# BMS.net
KiCad netlist of a schematic drawn in EAGLE
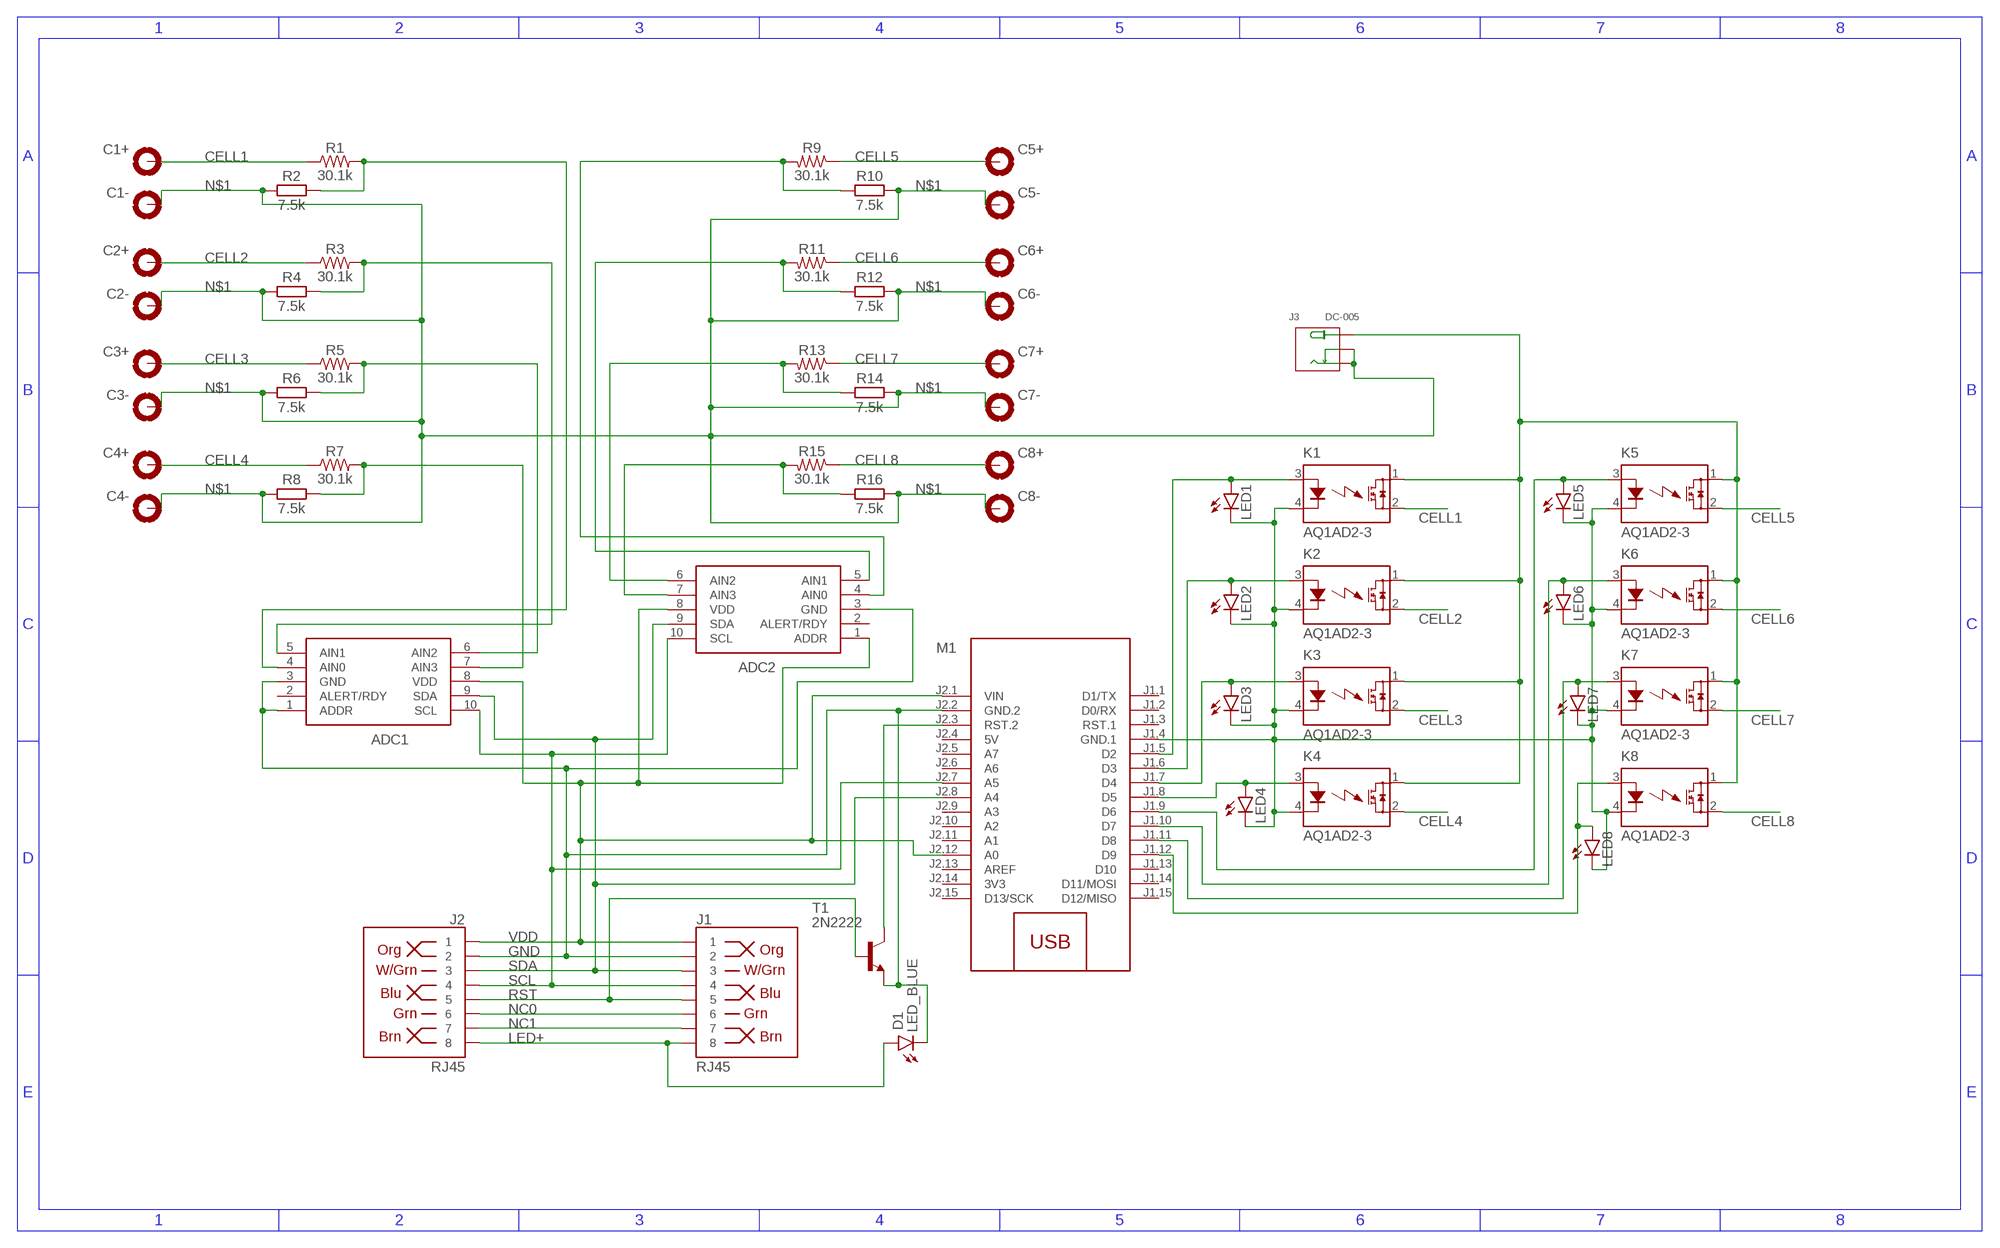
[diagram p0: schematic, sheet 1]

(export (version "E")
  (design (tool "Eeschema 10.0.6"))
  (components
    (comp (ref "ADC1")
      (value "ADS1115IDGST")
      (footprint "eagle-import:SOP50P490X110-10N")
      (fields (field (name "MOUSER_PART_NUMBER") "595-ADS1115IDGST"))
      (libsource (lib "eagle-import") (part "ADS1115IDGST"))
    )
    (comp (ref "ADC2")
      (value "ADS1115IDGST")
      (footprint "eagle-import:SOP50P490X110-10N")
      (fields (field (name "MOUSER_PART_NUMBER") "595-ADS1115IDGST"))
      (libsource (lib "eagle-import") (part "ADS1115IDGST"))
    )
    (comp (ref "C1+")
      (value "HOLES_MOUNT-PAD-ROUND-0.096-NS")
      (footprint "eagle-import:HOLES_096-PAD-NS")
      (libsource (lib "eagle-import") (part "HOLES_MOUNT-PAD-ROUND-0.096-NS"))
    )
    (comp (ref "C1-")
      (value "HOLES_MOUNT-PAD-ROUND-0.096-NS")
      (footprint "eagle-import:HOLES_096-PAD-NS")
      (libsource (lib "eagle-import") (part "HOLES_MOUNT-PAD-ROUND-0.096-NS"))
    )
    (comp (ref "C2+")
      (value "HOLES_MOUNT-PAD-ROUND-0.096-NS")
      (footprint "eagle-import:HOLES_096-PAD-NS")
      (libsource (lib "eagle-import") (part "HOLES_MOUNT-PAD-ROUND-0.096-NS"))
    )
    (comp (ref "C2-")
      (value "HOLES_MOUNT-PAD-ROUND-0.096-NS")
      (footprint "eagle-import:HOLES_096-PAD-NS")
      (libsource (lib "eagle-import") (part "HOLES_MOUNT-PAD-ROUND-0.096-NS"))
    )
    (comp (ref "C3+")
      (value "HOLES_MOUNT-PAD-ROUND-0.096-NS")
      (footprint "eagle-import:HOLES_096-PAD-NS")
      (libsource (lib "eagle-import") (part "HOLES_MOUNT-PAD-ROUND-0.096-NS"))
    )
    (comp (ref "C3-")
      (value "HOLES_MOUNT-PAD-ROUND-0.096-NS")
      (footprint "eagle-import:HOLES_096-PAD-NS")
      (libsource (lib "eagle-import") (part "HOLES_MOUNT-PAD-ROUND-0.096-NS"))
    )
    (comp (ref "C4+")
      (value "HOLES_MOUNT-PAD-ROUND-0.096-NS")
      (footprint "eagle-import:HOLES_096-PAD-NS")
      (libsource (lib "eagle-import") (part "HOLES_MOUNT-PAD-ROUND-0.096-NS"))
    )
    (comp (ref "C4-")
      (value "HOLES_MOUNT-PAD-ROUND-0.096-NS")
      (footprint "eagle-import:HOLES_096-PAD-NS")
      (libsource (lib "eagle-import") (part "HOLES_MOUNT-PAD-ROUND-0.096-NS"))
    )
    (comp (ref "C5+")
      (value "HOLES_MOUNT-PAD-ROUND-0.096-NS")
      (footprint "eagle-import:HOLES_096-PAD-NS")
      (libsource (lib "eagle-import") (part "HOLES_MOUNT-PAD-ROUND-0.096-NS"))
    )
    (comp (ref "C5-")
      (value "HOLES_MOUNT-PAD-ROUND-0.096-NS")
      (footprint "eagle-import:HOLES_096-PAD-NS")
      (libsource (lib "eagle-import") (part "HOLES_MOUNT-PAD-ROUND-0.096-NS"))
    )
    (comp (ref "C6+")
      (value "HOLES_MOUNT-PAD-ROUND-0.096-NS")
      (footprint "eagle-import:HOLES_096-PAD-NS")
      (libsource (lib "eagle-import") (part "HOLES_MOUNT-PAD-ROUND-0.096-NS"))
    )
    (comp (ref "C6-")
      (value "HOLES_MOUNT-PAD-ROUND-0.096-NS")
      (footprint "eagle-import:HOLES_096-PAD-NS")
      (libsource (lib "eagle-import") (part "HOLES_MOUNT-PAD-ROUND-0.096-NS"))
    )
    (comp (ref "C7+")
      (value "HOLES_MOUNT-PAD-ROUND-0.096-NS")
      (footprint "eagle-import:HOLES_096-PAD-NS")
      (libsource (lib "eagle-import") (part "HOLES_MOUNT-PAD-ROUND-0.096-NS"))
    )
    (comp (ref "C7-")
      (value "HOLES_MOUNT-PAD-ROUND-0.096-NS")
      (footprint "eagle-import:HOLES_096-PAD-NS")
      (libsource (lib "eagle-import") (part "HOLES_MOUNT-PAD-ROUND-0.096-NS"))
    )
    (comp (ref "C8+")
      (value "HOLES_MOUNT-PAD-ROUND-0.096-NS")
      (footprint "eagle-import:HOLES_096-PAD-NS")
      (libsource (lib "eagle-import") (part "HOLES_MOUNT-PAD-ROUND-0.096-NS"))
    )
    (comp (ref "C8-")
      (value "HOLES_MOUNT-PAD-ROUND-0.096-NS")
      (footprint "eagle-import:HOLES_096-PAD-NS")
      (libsource (lib "eagle-import") (part "HOLES_MOUNT-PAD-ROUND-0.096-NS"))
    )
    (comp (ref "D1")
      (value "LED_BLUE")
      (footprint "eagle-import:LEDRD254W60D565H860B_B")
      (libsource (lib "eagle-import") (part "LED_RADIALBLUE_"))
    )
    (comp (ref "J1")
      (value "RJ45")
      (footprint "eagle-import:RJ45-8")
      (libsource (lib "eagle-import") (part "RJ45-8"))
    )
    (comp (ref "J2")
      (value "RJ45")
      (footprint "eagle-import:RJ45-8")
      (libsource (lib "eagle-import") (part "RJ45-8"))
    )
    (comp (ref "J3")
      (value "DC-005")
      (footprint "eagle-import:DCJ3P-14.2X11.0X9.0MM")
      (libsource (lib "eagle-import") (part "CONN-POWER-JACK-2.1MM(DC-005)"))
    )
    (comp (ref "K1")
      (value "AQ1AD2-3")
      (footprint "eagle-import:AQ1")
      (fields (field (name "MF") "AROMAT/ MATSUSHITA") (field (name "MPN") "AQ1AD2-3/28VDC"))
      (libsource (lib "eagle-import") (part "AQ1AD2-3"))
    )
    (comp (ref "K2")
      (value "AQ1AD2-3")
      (footprint "eagle-import:AQ1")
      (fields (field (name "MF") "AROMAT/ MATSUSHITA") (field (name "MPN") "AQ1AD2-3/28VDC"))
      (libsource (lib "eagle-import") (part "AQ1AD2-3"))
    )
    (comp (ref "K3")
      (value "AQ1AD2-3")
      (footprint "eagle-import:AQ1")
      (fields (field (name "MF") "AROMAT/ MATSUSHITA") (field (name "MPN") "AQ1AD2-3/28VDC"))
      (libsource (lib "eagle-import") (part "AQ1AD2-3"))
    )
    (comp (ref "K4")
      (value "AQ1AD2-3")
      (footprint "eagle-import:AQ1")
      (fields (field (name "MF") "AROMAT/ MATSUSHITA") (field (name "MPN") "AQ1AD2-3/28VDC"))
      (libsource (lib "eagle-import") (part "AQ1AD2-3"))
    )
    (comp (ref "K5")
      (value "AQ1AD2-3")
      (footprint "eagle-import:AQ1")
      (fields (field (name "MF") "AROMAT/ MATSUSHITA") (field (name "MPN") "AQ1AD2-3/28VDC"))
      (libsource (lib "eagle-import") (part "AQ1AD2-3"))
    )
    (comp (ref "K6")
      (value "AQ1AD2-3")
      (footprint "eagle-import:AQ1")
      (fields (field (name "MF") "AROMAT/ MATSUSHITA") (field (name "MPN") "AQ1AD2-3/28VDC"))
      (libsource (lib "eagle-import") (part "AQ1AD2-3"))
    )
    (comp (ref "K7")
      (value "AQ1AD2-3")
      (footprint "eagle-import:AQ1")
      (fields (field (name "MF") "AROMAT/ MATSUSHITA") (field (name "MPN") "AQ1AD2-3/28VDC"))
      (libsource (lib "eagle-import") (part "AQ1AD2-3"))
    )
    (comp (ref "K8")
      (value "AQ1AD2-3")
      (footprint "eagle-import:AQ1")
      (fields (field (name "MF") "AROMAT/ MATSUSHITA") (field (name "MPN") "AQ1AD2-3/28VDC"))
      (libsource (lib "eagle-import") (part "AQ1AD2-3"))
    )
    (comp (ref "LED1")
      (value "LEDCHIP-LED0805")
      (footprint "eagle-import:CHIP-LED0805")
      (libsource (lib "eagle-import") (part "LEDCHIP-LED0805"))
    )
    (comp (ref "LED2")
      (value "LEDCHIP-LED0805")
      (footprint "eagle-import:CHIP-LED0805")
      (libsource (lib "eagle-import") (part "LEDCHIP-LED0805"))
    )
    (comp (ref "LED3")
      (value "LEDCHIP-LED0805")
      (footprint "eagle-import:CHIP-LED0805")
      (libsource (lib "eagle-import") (part "LEDCHIP-LED0805"))
    )
    (comp (ref "LED4")
      (value "LEDCHIP-LED0805")
      (footprint "eagle-import:CHIP-LED0805")
      (libsource (lib "eagle-import") (part "LEDCHIP-LED0805"))
    )
    (comp (ref "LED5")
      (value "LEDCHIP-LED0805")
      (footprint "eagle-import:CHIP-LED0805")
      (libsource (lib "eagle-import") (part "LEDCHIP-LED0805"))
    )
    (comp (ref "LED6")
      (value "LEDCHIP-LED0805")
      (footprint "eagle-import:CHIP-LED0805")
      (libsource (lib "eagle-import") (part "LEDCHIP-LED0805"))
    )
    (comp (ref "LED7")
      (value "LEDCHIP-LED0805")
      (footprint "eagle-import:CHIP-LED0805")
      (libsource (lib "eagle-import") (part "LEDCHIP-LED0805"))
    )
    (comp (ref "LED8")
      (value "LEDCHIP-LED0805")
      (footprint "eagle-import:CHIP-LED0805")
      (libsource (lib "eagle-import") (part "LEDCHIP-LED0805"))
    )
    (comp (ref "M1")
      (value "ARDUINO-NANO-3.0")
      (footprint "eagle-import:ARDUINO-NANO-3.0")
      (libsource (lib "eagle-import") (part "ARDUINO-NANO-3.0"))
    )
    (comp (ref "R1")
      (value "30.1k")
      (footprint "eagle-import:0603")
      (libsource (lib "eagle-import") (part "30.1KOHM-0603-1/10W-1%"))
    )
    (comp (ref "R2")
      (value "7.5k")
      (footprint "eagle-import:RESC3216X70")
      (libsource (lib "eagle-import") (part "RESISTOR_CHIP-1206(3216-METRIC)_"))
    )
    (comp (ref "R3")
      (value "30.1k")
      (footprint "eagle-import:0603")
      (libsource (lib "eagle-import") (part "30.1KOHM-0603-1/10W-1%"))
    )
    (comp (ref "R4")
      (value "7.5k")
      (footprint "eagle-import:RESC3216X70")
      (libsource (lib "eagle-import") (part "RESISTOR_CHIP-1206(3216-METRIC)_"))
    )
    (comp (ref "R5")
      (value "30.1k")
      (footprint "eagle-import:0603")
      (libsource (lib "eagle-import") (part "30.1KOHM-0603-1/10W-1%"))
    )
    (comp (ref "R6")
      (value "7.5k")
      (footprint "eagle-import:RESC3216X70")
      (libsource (lib "eagle-import") (part "RESISTOR_CHIP-1206(3216-METRIC)_"))
    )
    (comp (ref "R7")
      (value "30.1k")
      (footprint "eagle-import:0603")
      (libsource (lib "eagle-import") (part "30.1KOHM-0603-1/10W-1%"))
    )
    (comp (ref "R8")
      (value "7.5k")
      (footprint "eagle-import:RESC3216X70")
      (libsource (lib "eagle-import") (part "RESISTOR_CHIP-1206(3216-METRIC)_"))
    )
    (comp (ref "R9")
      (value "30.1k")
      (footprint "eagle-import:0603")
      (libsource (lib "eagle-import") (part "30.1KOHM-0603-1/10W-1%"))
    )
    (comp (ref "R10")
      (value "7.5k")
      (footprint "eagle-import:RESC3216X70")
      (libsource (lib "eagle-import") (part "RESISTOR_CHIP-1206(3216-METRIC)_"))
    )
    (comp (ref "R11")
      (value "30.1k")
      (footprint "eagle-import:0603")
      (libsource (lib "eagle-import") (part "30.1KOHM-0603-1/10W-1%"))
    )
    (comp (ref "R12")
      (value "7.5k")
      (footprint "eagle-import:RESC3216X70")
      (libsource (lib "eagle-import") (part "RESISTOR_CHIP-1206(3216-METRIC)_"))
    )
    (comp (ref "R13")
      (value "30.1k")
      (footprint "eagle-import:0603")
      (libsource (lib "eagle-import") (part "30.1KOHM-0603-1/10W-1%"))
    )
    (comp (ref "R14")
      (value "7.5k")
      (footprint "eagle-import:RESC3216X70")
      (libsource (lib "eagle-import") (part "RESISTOR_CHIP-1206(3216-METRIC)_"))
    )
    (comp (ref "R15")
      (value "30.1k")
      (footprint "eagle-import:0603")
      (libsource (lib "eagle-import") (part "30.1KOHM-0603-1/10W-1%"))
    )
    (comp (ref "R16")
      (value "7.5k")
      (footprint "eagle-import:RESC3216X70")
      (libsource (lib "eagle-import") (part "RESISTOR_CHIP-1206(3216-METRIC)_"))
    )
    (comp (ref "T1")
      (value "2N2222")
      (footprint "eagle-import:TO18")
      (libsource (lib "eagle-import") (part "2N2222"))
    )
  )
  (nets
    (net (code "1") (name "/3V3") (class "Default")
      (node (ref "M1") (pin "J2.14") (pinfunction "3V3_J2.14") (pintype "power_in"))
    )
    (net (code "2") (name "/5V") (class "Default")
      (node (ref "M1") (pin "J2.4") (pinfunction "5V_J2.4") (pintype "power_in"))
    )
    (net (code "3") (name "/CELL1") (class "Default")
      (node (ref "C1+") (pin "B096") (pinfunction "MOUNT_B096") (pintype "passive"))
      (node (ref "K1") (pin "2") (pinfunction "DS2_2") (pintype "passive"))
      (node (ref "R1") (pin "1") (pinfunction "1_1") (pintype "passive"))
    )
    (net (code "4") (name "/CELL2") (class "Default")
      (node (ref "C2+") (pin "B096") (pinfunction "MOUNT_B096") (pintype "passive"))
      (node (ref "K2") (pin "2") (pinfunction "DS2_2") (pintype "passive"))
      (node (ref "R3") (pin "1") (pinfunction "1_1") (pintype "passive"))
    )
    (net (code "5") (name "/CELL3") (class "Default")
      (node (ref "C3+") (pin "B096") (pinfunction "MOUNT_B096") (pintype "passive"))
      (node (ref "K3") (pin "2") (pinfunction "DS2_2") (pintype "passive"))
      (node (ref "R5") (pin "1") (pinfunction "1_1") (pintype "passive"))
    )
    (net (code "6") (name "/CELL4") (class "Default")
      (node (ref "C4+") (pin "B096") (pinfunction "MOUNT_B096") (pintype "passive"))
      (node (ref "K4") (pin "2") (pinfunction "DS2_2") (pintype "passive"))
      (node (ref "R7") (pin "1") (pinfunction "1_1") (pintype "passive"))
    )
    (net (code "7") (name "/CELL5") (class "Default")
      (node (ref "C5+") (pin "B096") (pinfunction "MOUNT_B096") (pintype "passive"))
      (node (ref "K5") (pin "2") (pinfunction "DS2_2") (pintype "passive"))
      (node (ref "R9") (pin "1") (pinfunction "1_1") (pintype "passive"))
    )
    (net (code "8") (name "/CELL6") (class "Default")
      (node (ref "C6+") (pin "B096") (pinfunction "MOUNT_B096") (pintype "passive"))
      (node (ref "K6") (pin "2") (pinfunction "DS2_2") (pintype "passive"))
      (node (ref "R11") (pin "1") (pinfunction "1_1") (pintype "passive"))
    )
    (net (code "9") (name "/CELL7") (class "Default")
      (node (ref "C7+") (pin "B096") (pinfunction "MOUNT_B096") (pintype "passive"))
      (node (ref "K7") (pin "2") (pinfunction "DS2_2") (pintype "passive"))
      (node (ref "R13") (pin "1") (pinfunction "1_1") (pintype "passive"))
    )
    (net (code "10") (name "/CELL8") (class "Default")
      (node (ref "C8+") (pin "B096") (pinfunction "MOUNT_B096") (pintype "passive"))
      (node (ref "K8") (pin "2") (pinfunction "DS2_2") (pintype "passive"))
      (node (ref "R15") (pin "1") (pinfunction "1_1") (pintype "passive"))
    )
    (net (code "11") (name "/GND") (class "Default")
      (node (ref "ADC1") (pin "1") (pinfunction "ADDR_1") (pintype "bidirectional"))
      (node (ref "ADC1") (pin "3") (pinfunction "GND_3") (pintype "bidirectional"))
      (node (ref "ADC2") (pin "3") (pinfunction "GND_3") (pintype "bidirectional"))
      (node (ref "D1") (pin "2") (pinfunction "C_2") (pintype "passive"))
      (node (ref "J1") (pin "2") (pinfunction "2_2") (pintype "bidirectional"))
      (node (ref "J2") (pin "2") (pinfunction "2_2") (pintype "bidirectional"))
      (node (ref "M1") (pin "J2.2") (pinfunction "GND.2_J2.2") (pintype "power_in"))
      (node (ref "T1") (pin "1") (pinfunction "E_1") (pintype "passive"))
    )
    (net (code "12") (name "/LED+") (class "Default")
      (node (ref "D1") (pin "1") (pinfunction "A_1") (pintype "passive"))
      (node (ref "J1") (pin "8") (pinfunction "8_8") (pintype "bidirectional"))
      (node (ref "J2") (pin "8") (pinfunction "8_8") (pintype "bidirectional"))
    )
    (net (code "13") (name "/N$1") (class "Default")
      (node (ref "C1-") (pin "B096") (pinfunction "MOUNT_B096") (pintype "passive"))
      (node (ref "C2-") (pin "B096") (pinfunction "MOUNT_B096") (pintype "passive"))
      (node (ref "C3-") (pin "B096") (pinfunction "MOUNT_B096") (pintype "passive"))
      (node (ref "C4-") (pin "B096") (pinfunction "MOUNT_B096") (pintype "passive"))
      (node (ref "C5-") (pin "B096") (pinfunction "MOUNT_B096") (pintype "passive"))
      (node (ref "C6-") (pin "B096") (pinfunction "MOUNT_B096") (pintype "passive"))
      (node (ref "C7-") (pin "B096") (pinfunction "MOUNT_B096") (pintype "passive"))
      (node (ref "C8-") (pin "B096") (pinfunction "MOUNT_B096") (pintype "passive"))
      (node (ref "J3") (pin "-1B") (pinfunction "-_-1B") (pintype "bidirectional"))
      (node (ref "J3") (pin "-1T") (pinfunction "-_-1T") (pintype "bidirectional"))
      (node (ref "J3") (pin "-2") (pinfunction "CDN_-2") (pintype "bidirectional"))
      (node (ref "J3") (pin "-2B") (pinfunction "CDN_-2B") (pintype "bidirectional"))
      (node (ref "R10") (pin "1") (pinfunction "1_1") (pintype "passive"))
      (node (ref "R12") (pin "1") (pinfunction "1_1") (pintype "passive"))
      (node (ref "R14") (pin "1") (pinfunction "1_1") (pintype "passive"))
      (node (ref "R16") (pin "1") (pinfunction "1_1") (pintype "passive"))
      (node (ref "R2") (pin "1") (pinfunction "1_1") (pintype "passive"))
      (node (ref "R4") (pin "1") (pinfunction "1_1") (pintype "passive"))
      (node (ref "R6") (pin "1") (pinfunction "1_1") (pintype "passive"))
      (node (ref "R8") (pin "1") (pinfunction "1_1") (pintype "passive"))
    )
    (net (code "14") (name "/NC0") (class "Default")
      (node (ref "J1") (pin "6") (pinfunction "6_6") (pintype "bidirectional"))
      (node (ref "J2") (pin "6") (pinfunction "6_6") (pintype "bidirectional"))
    )
    (net (code "15") (name "/NC1") (class "Default")
      (node (ref "J1") (pin "7") (pinfunction "7_7") (pintype "bidirectional"))
      (node (ref "J2") (pin "7") (pinfunction "7_7") (pintype "bidirectional"))
    )
    (net (code "16") (name "/RST") (class "Default")
      (node (ref "J1") (pin "5") (pinfunction "5_5") (pintype "bidirectional"))
      (node (ref "J2") (pin "5") (pinfunction "5_5") (pintype "bidirectional"))
      (node (ref "T1") (pin "2") (pinfunction "B_2") (pintype "passive"))
    )
    (net (code "17") (name "/SCL") (class "Default")
      (node (ref "ADC1") (pin "10") (pinfunction "SCL_10") (pintype "bidirectional"))
      (node (ref "ADC2") (pin "10") (pinfunction "SCL_10") (pintype "bidirectional"))
      (node (ref "J1") (pin "4") (pinfunction "4_4") (pintype "bidirectional"))
      (node (ref "J2") (pin "4") (pinfunction "4_4") (pintype "bidirectional"))
      (node (ref "M1") (pin "J2.7") (pinfunction "A5_J2.7") (pintype "bidirectional"))
    )
    (net (code "18") (name "/SDA") (class "Default")
      (node (ref "ADC1") (pin "9") (pinfunction "SDA_9") (pintype "bidirectional"))
      (node (ref "ADC2") (pin "9") (pinfunction "SDA_9") (pintype "bidirectional"))
      (node (ref "J1") (pin "3") (pinfunction "3_3") (pintype "bidirectional"))
      (node (ref "J2") (pin "3") (pinfunction "3_3") (pintype "bidirectional"))
      (node (ref "M1") (pin "J2.8") (pinfunction "A4_J2.8") (pintype "bidirectional"))
    )
    (net (code "19") (name "/VDD") (class "Default")
      (node (ref "ADC1") (pin "8") (pinfunction "VDD_8") (pintype "bidirectional"))
      (node (ref "ADC2") (pin "1") (pinfunction "ADDR_1") (pintype "bidirectional"))
      (node (ref "ADC2") (pin "8") (pinfunction "VDD_8") (pintype "bidirectional"))
      (node (ref "J1") (pin "1") (pinfunction "1_1") (pintype "bidirectional"))
      (node (ref "J2") (pin "1") (pinfunction "1_1") (pintype "bidirectional"))
      (node (ref "M1") (pin "J2.1") (pinfunction "VIN_J2.1") (pintype "power_in"))
      (node (ref "M1") (pin "J2.12") (pinfunction "A0_J2.12") (pintype "bidirectional"))
    )
    (net (code "20") (name "Net-(ADC1-AIN0)") (class "Default")
      (node (ref "ADC1") (pin "4") (pinfunction "AIN0_4") (pintype "bidirectional"))
      (node (ref "R1") (pin "2") (pinfunction "2_2") (pintype "passive"))
      (node (ref "R2") (pin "2") (pinfunction "2_2") (pintype "passive"))
    )
    (net (code "21") (name "Net-(ADC1-AIN1)") (class "Default")
      (node (ref "ADC1") (pin "5") (pinfunction "AIN1_5") (pintype "bidirectional"))
      (node (ref "R3") (pin "2") (pinfunction "2_2") (pintype "passive"))
      (node (ref "R4") (pin "2") (pinfunction "2_2") (pintype "passive"))
    )
    (net (code "22") (name "Net-(ADC1-AIN2)") (class "Default")
      (node (ref "ADC1") (pin "6") (pinfunction "AIN2_6") (pintype "bidirectional"))
      (node (ref "R5") (pin "2") (pinfunction "2_2") (pintype "passive"))
      (node (ref "R6") (pin "2") (pinfunction "2_2") (pintype "passive"))
    )
    (net (code "23") (name "Net-(ADC1-AIN3)") (class "Default")
      (node (ref "ADC1") (pin "7") (pinfunction "AIN3_7") (pintype "bidirectional"))
      (node (ref "R7") (pin "2") (pinfunction "2_2") (pintype "passive"))
      (node (ref "R8") (pin "2") (pinfunction "2_2") (pintype "passive"))
    )
    (net (code "24") (name "Net-(ADC2-AIN0)") (class "Default")
      (node (ref "ADC2") (pin "4") (pinfunction "AIN0_4") (pintype "bidirectional"))
      (node (ref "R10") (pin "2") (pinfunction "2_2") (pintype "passive"))
      (node (ref "R9") (pin "2") (pinfunction "2_2") (pintype "passive"))
    )
    (net (code "25") (name "Net-(ADC2-AIN1)") (class "Default")
      (node (ref "ADC2") (pin "5") (pinfunction "AIN1_5") (pintype "bidirectional"))
      (node (ref "R11") (pin "2") (pinfunction "2_2") (pintype "passive"))
      (node (ref "R12") (pin "2") (pinfunction "2_2") (pintype "passive"))
    )
    (net (code "26") (name "Net-(ADC2-AIN2)") (class "Default")
      (node (ref "ADC2") (pin "6") (pinfunction "AIN2_6") (pintype "bidirectional"))
      (node (ref "R13") (pin "2") (pinfunction "2_2") (pintype "passive"))
      (node (ref "R14") (pin "2") (pinfunction "2_2") (pintype "passive"))
    )
    (net (code "27") (name "Net-(ADC2-AIN3)") (class "Default")
      (node (ref "ADC2") (pin "7") (pinfunction "AIN3_7") (pintype "bidirectional"))
      (node (ref "R15") (pin "2") (pinfunction "2_2") (pintype "passive"))
      (node (ref "R16") (pin "2") (pinfunction "2_2") (pintype "passive"))
    )
    (net (code "28") (name "Net-(K1-A)") (class "Default")
      (node (ref "K1") (pin "3") (pinfunction "A_3") (pintype "passive"))
      (node (ref "LED1") (pin "A") (pinfunction "A_A") (pintype "passive"))
      (node (ref "M1") (pin "J1.5") (pinfunction "D2_J1.5") (pintype "bidirectional"))
    )
    (net (code "29") (name "Net-(K1-DS1)") (class "Default")
      (node (ref "J3") (pin "+B") (pinfunction "+_+B") (pintype "bidirectional"))
      (node (ref "J3") (pin "+T") (pinfunction "+_+T") (pintype "bidirectional"))
      (node (ref "K1") (pin "1") (pinfunction "DS1_1") (pintype "passive"))
      (node (ref "K2") (pin "1") (pinfunction "DS1_1") (pintype "passive"))
      (node (ref "K3") (pin "1") (pinfunction "DS1_1") (pintype "passive"))
      (node (ref "K4") (pin "1") (pinfunction "DS1_1") (pintype "passive"))
      (node (ref "K5") (pin "1") (pinfunction "DS1_1") (pintype "passive"))
      (node (ref "K6") (pin "1") (pinfunction "DS1_1") (pintype "passive"))
      (node (ref "K7") (pin "1") (pinfunction "DS1_1") (pintype "passive"))
      (node (ref "K8") (pin "1") (pinfunction "DS1_1") (pintype "passive"))
    )
    (net (code "30") (name "Net-(K1-K)") (class "Default")
      (node (ref "K1") (pin "4") (pinfunction "K_4") (pintype "passive"))
      (node (ref "K2") (pin "4") (pinfunction "K_4") (pintype "passive"))
      (node (ref "K3") (pin "4") (pinfunction "K_4") (pintype "passive"))
      (node (ref "K4") (pin "4") (pinfunction "K_4") (pintype "passive"))
      (node (ref "K5") (pin "4") (pinfunction "K_4") (pintype "passive"))
      (node (ref "K6") (pin "4") (pinfunction "K_4") (pintype "passive"))
      (node (ref "K7") (pin "4") (pinfunction "K_4") (pintype "passive"))
      (node (ref "K8") (pin "4") (pinfunction "K_4") (pintype "passive"))
      (node (ref "LED1") (pin "C") (pinfunction "C_C") (pintype "passive"))
      (node (ref "LED2") (pin "C") (pinfunction "C_C") (pintype "passive"))
      (node (ref "LED3") (pin "C") (pinfunction "C_C") (pintype "passive"))
      (node (ref "LED4") (pin "C") (pinfunction "C_C") (pintype "passive"))
      (node (ref "LED5") (pin "C") (pinfunction "C_C") (pintype "passive"))
      (node (ref "LED6") (pin "C") (pinfunction "C_C") (pintype "passive"))
      (node (ref "LED7") (pin "C") (pinfunction "C_C") (pintype "passive"))
      (node (ref "LED8") (pin "C") (pinfunction "C_C") (pintype "passive"))
      (node (ref "M1") (pin "J1.4") (pinfunction "GND.1_J1.4") (pintype "power_in"))
    )
    (net (code "31") (name "Net-(K2-A)") (class "Default")
      (node (ref "K2") (pin "3") (pinfunction "A_3") (pintype "passive"))
      (node (ref "LED2") (pin "A") (pinfunction "A_A") (pintype "passive"))
      (node (ref "M1") (pin "J1.6") (pinfunction "D3_J1.6") (pintype "bidirectional"))
    )
    (net (code "32") (name "Net-(K3-A)") (class "Default")
      (node (ref "K3") (pin "3") (pinfunction "A_3") (pintype "passive"))
      (node (ref "LED3") (pin "A") (pinfunction "A_A") (pintype "passive"))
      (node (ref "M1") (pin "J1.7") (pinfunction "D4_J1.7") (pintype "bidirectional"))
    )
    (net (code "33") (name "Net-(K4-A)") (class "Default")
      (node (ref "K4") (pin "3") (pinfunction "A_3") (pintype "passive"))
      (node (ref "LED4") (pin "A") (pinfunction "A_A") (pintype "passive"))
      (node (ref "M1") (pin "J1.8") (pinfunction "D5_J1.8") (pintype "bidirectional"))
    )
    (net (code "34") (name "Net-(K5-A)") (class "Default")
      (node (ref "K5") (pin "3") (pinfunction "A_3") (pintype "passive"))
      (node (ref "LED5") (pin "A") (pinfunction "A_A") (pintype "passive"))
      (node (ref "M1") (pin "J1.9") (pinfunction "D6_J1.9") (pintype "bidirectional"))
    )
    (net (code "35") (name "Net-(K6-A)") (class "Default")
      (node (ref "K6") (pin "3") (pinfunction "A_3") (pintype "passive"))
      (node (ref "LED6") (pin "A") (pinfunction "A_A") (pintype "passive"))
      (node (ref "M1") (pin "J1.10") (pinfunction "D7_J1.10") (pintype "bidirectional"))
    )
    (net (code "36") (name "Net-(K7-A)") (class "Default")
      (node (ref "K7") (pin "3") (pinfunction "A_3") (pintype "passive"))
      (node (ref "LED7") (pin "A") (pinfunction "A_A") (pintype "passive"))
      (node (ref "M1") (pin "J1.11") (pinfunction "D8_J1.11") (pintype "bidirectional"))
    )
    (net (code "37") (name "Net-(K8-A)") (class "Default")
      (node (ref "K8") (pin "3") (pinfunction "A_3") (pintype "passive"))
      (node (ref "LED8") (pin "A") (pinfunction "A_A") (pintype "passive"))
      (node (ref "M1") (pin "J1.12") (pinfunction "D9_J1.12") (pintype "bidirectional"))
    )
    (net (code "38") (name "Net-(M1-RST.2)") (class "Default")
      (node (ref "M1") (pin "J2.3") (pinfunction "RST.2_J2.3") (pintype "bidirectional"))
      (node (ref "T1") (pin "3") (pinfunction "C_3") (pintype "passive"))
    )
    (net (code "39") (name "unconnected-(ADC1-ALERT{slash}RDY-Pad2)") (class "Default")
      (node (ref "ADC1") (pin "2") (pinfunction "ALERT/RDY_2") (pintype "bidirectional"))
    )
    (net (code "40") (name "unconnected-(ADC2-ALERT{slash}RDY-Pad2)") (class "Default")
      (node (ref "ADC2") (pin "2") (pinfunction "ALERT/RDY_2") (pintype "bidirectional"))
    )
    (net (code "41") (name "unconnected-(M1-A1-PadJ2.11)") (class "Default")
      (node (ref "M1") (pin "J2.11") (pinfunction "A1_J2.11") (pintype "bidirectional"))
    )
    (net (code "42") (name "unconnected-(M1-A2-PadJ2.10)") (class "Default")
      (node (ref "M1") (pin "J2.10") (pinfunction "A2_J2.10") (pintype "bidirectional"))
    )
    (net (code "43") (name "unconnected-(M1-A3-PadJ2.9)") (class "Default")
      (node (ref "M1") (pin "J2.9") (pinfunction "A3_J2.9") (pintype "bidirectional"))
    )
    (net (code "44") (name "unconnected-(M1-A6-PadJ2.6)") (class "Default")
      (node (ref "M1") (pin "J2.6") (pinfunction "A6_J2.6") (pintype "bidirectional"))
    )
    (net (code "45") (name "unconnected-(M1-A7-PadJ2.5)") (class "Default")
      (node (ref "M1") (pin "J2.5") (pinfunction "A7_J2.5") (pintype "bidirectional"))
    )
    (net (code "46") (name "unconnected-(M1-AREF-PadJ2.13)") (class "Default")
      (node (ref "M1") (pin "J2.13") (pinfunction "AREF_J2.13") (pintype "bidirectional"))
    )
    (net (code "47") (name "unconnected-(M1-D0{slash}RX-PadJ1.2)") (class "Default")
      (node (ref "M1") (pin "J1.2") (pinfunction "D0/RX_J1.2") (pintype "bidirectional"))
    )
    (net (code "48") (name "unconnected-(M1-D1{slash}TX-PadJ1.1)") (class "Default")
      (node (ref "M1") (pin "J1.1") (pinfunction "D1/TX_J1.1") (pintype "bidirectional"))
    )
    (net (code "49") (name "unconnected-(M1-D10-PadJ1.13)") (class "Default")
      (node (ref "M1") (pin "J1.13") (pinfunction "D10_J1.13") (pintype "bidirectional"))
    )
    (net (code "50") (name "unconnected-(M1-D11{slash}MOSI-PadJ1.14)") (class "Default")
      (node (ref "M1") (pin "J1.14") (pinfunction "D11/MOSI_J1.14") (pintype "bidirectional"))
    )
    (net (code "51") (name "unconnected-(M1-D12{slash}MISO-PadJ1.15)") (class "Default")
      (node (ref "M1") (pin "J1.15") (pinfunction "D12/MISO_J1.15") (pintype "bidirectional"))
    )
    (net (code "52") (name "unconnected-(M1-D13{slash}SCK-PadJ2.15)") (class "Default")
      (node (ref "M1") (pin "J2.15") (pinfunction "D13/SCK_J2.15") (pintype "bidirectional"))
    )
    (net (code "53") (name "unconnected-(M1-RST.1-PadJ1.3)") (class "Default")
      (node (ref "M1") (pin "J1.3") (pinfunction "RST.1_J1.3") (pintype "bidirectional"))
    )
  )
)
